# RS-485.net
KiCad netlist of a schematic drawn in Altium Designer
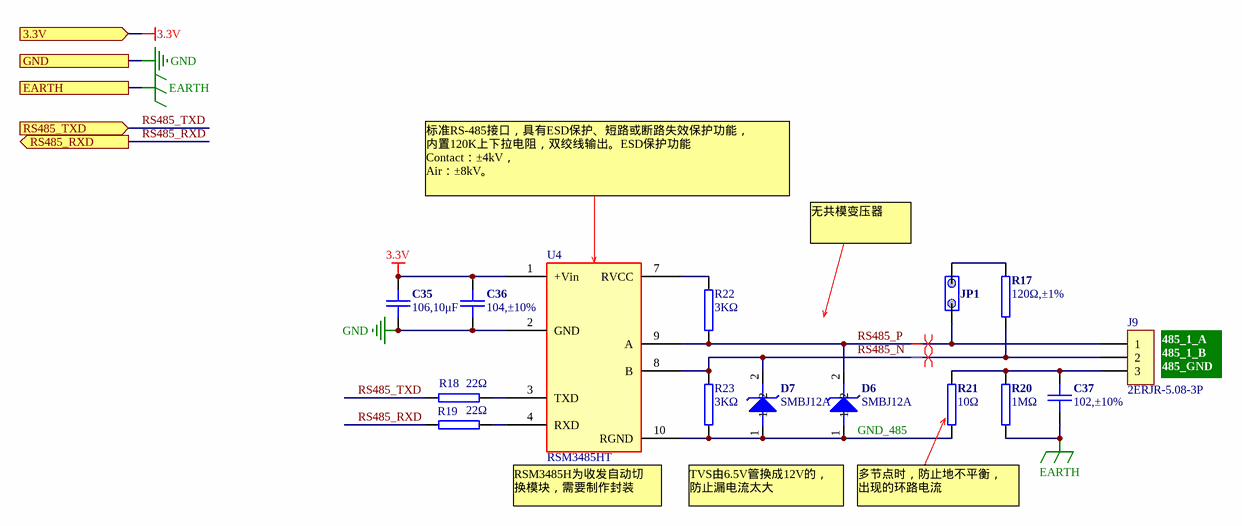
[diagram p0: RS-485推荐电路.SchDoc]

(export (version "E")
  (design (tool "Eeschema 10.0.6"))
  (components
    (comp (ref "C35")
      (value "106,10μF")
      (footprint "0805C")
      (description "106,10μF,±10%,10V,X5R,0805,RoHS")
      (libsource (lib "ErpMaterialData") (part "CAP1"))
    )
    (comp (ref "C36")
      (value "104,±10%")
      (footprint "0603C")
      (description "104,±10%,50V,X7R,0603,*,RoHS")
      (libsource (lib "ErpMaterialData") (part "CAP1"))
    )
    (comp (ref "C37")
      (value "102,±10%")
      (footprint "1206C")
      (description "102,±10%,2KV,X7R,1206,*,RoHS")
      (libsource (lib "ErpMaterialData") (part "CAP1"))
    )
    (comp (ref "D6")
      (value "SMBJ12A")
      (footprint "SOD-1812D")
      (description "SMBJ12A,DO-214AA,君耀,RoHS")
      (fields (field (name "Comment") "DIODE ZENER"))
      (libsource (lib "ErpMaterialData") (part "DIODE ZENER"))
    )
    (comp (ref "D7")
      (value "SMBJ12A")
      (footprint "SOD-1812D")
      (description "SMBJ12A,DO-214AA,君耀,RoHS")
      (fields (field (name "Comment") "DIODE ZENER"))
      (libsource (lib "ErpMaterialData") (part "DIODE ZENER"))
    )
    (comp (ref "J9")
      (value "2ERJR-5.08-3P")
      (footprint "CON-3-5.08")
      (fields (field (name "Comment") "CON3"))
      (libsource (lib "ErpMaterialData") (part "CON3"))
    )
    (comp (ref "JP1") (value "120Ω_EN") (footprint "SIP-2") (libsource (lib "无需物料号元件") (part "JMP2")))
    (comp (ref "R17")
      (value "120Ω,±1%")
      (footprint "1206R")
      (libsource (lib "ErpMaterialData") (part "RES2"))
    )
    (comp (ref "R18")
      (value "22Ω")
      (footprint "0603R")
      (description "22Ω,0603,*,RoHS")
      (libsource (lib "ErpMaterialData") (part "RES2"))
    )
    (comp (ref "R19")
      (value "22Ω")
      (footprint "0603R")
      (description "22Ω,0603,*,RoHS")
      (libsource (lib "ErpMaterialData") (part "RES2"))
    )
    (comp (ref "R20")
      (value "1MΩ")
      (footprint "1206R")
      (description "1MΩ,1206,RoHS")
      (libsource (lib "ErpMaterialData") (part "RES2"))
    )
    (comp (ref "R21")
      (value "10Ω")
      (footprint "0805R")
      (description "10Ω,0805,*,RoHS")
      (libsource (lib "ErpMaterialData") (part "RES2"))
    )
    (comp (ref "R22")
      (value "3KΩ")
      (footprint "0603R")
      (description "3KΩ,0603,*,RoHS")
      (libsource (lib "ErpMaterialData") (part "RES2"))
    )
    (comp (ref "R23")
      (value "3KΩ")
      (footprint "0603R")
      (description "3KΩ,0603,*,RoHS")
      (libsource (lib "ErpMaterialData") (part "RES2"))
    )
    (comp (ref "U4") (value "RSM3485HT") (libsource (lib "M6708_EV_BORAD") (part "RSM3485H")))
  )
  (nets
    (net (code "1") (name "/GND_485") (class "Default")
      (node (ref "D6") (pin "1") (pinfunction "1_1") (pintype "passive"))
      (node (ref "D7") (pin "1") (pinfunction "1_1") (pintype "passive"))
      (node (ref "R21") (pin "1") (pinfunction "1_1") (pintype "passive"))
      (node (ref "R23") (pin "2") (pinfunction "2_2") (pintype "passive"))
      (node (ref "U4") (pin "10") (pinfunction "RGND_10") (pintype "passive"))
    )
    (net (code "2") (name "/RS485_N") (class "Default")
      (node (ref "D7") (pin "2") (pinfunction "2_2") (pintype "passive"))
      (node (ref "J9") (pin "2") (pinfunction "2_2") (pintype "passive"))
      (node (ref "R17") (pin "2") (pinfunction "2_2") (pintype "passive"))
      (node (ref "R23") (pin "1") (pinfunction "1_1") (pintype "passive"))
      (node (ref "U4") (pin "8") (pinfunction "B_8") (pintype "passive"))
    )
    (net (code "3") (name "/RS485_P") (class "Default")
      (node (ref "D6") (pin "2") (pinfunction "2_2") (pintype "passive"))
      (node (ref "J9") (pin "1") (pinfunction "1_1") (pintype "passive"))
      (node (ref "JP1") (pin "1") (pinfunction "1_1") (pintype "passive"))
      (node (ref "R22") (pin "2") (pinfunction "2_2") (pintype "passive"))
      (node (ref "U4") (pin "9") (pinfunction "A_9") (pintype "passive"))
    )
    (net (code "4") (name "/RS485_RXD") (class "Default")
      (node (ref "R19") (pin "1") (pinfunction "1_1") (pintype "passive"))
    )
    (net (code "5") (name "/RS485_TXD") (class "Default")
      (node (ref "R18") (pin "1") (pinfunction "1_1") (pintype "passive"))
    )
    (net (code "6") (name "3.3V") (class "Default")
      (node (ref "C35") (pin "1") (pinfunction "1_1") (pintype "passive"))
      (node (ref "C36") (pin "1") (pinfunction "1_1") (pintype "passive"))
      (node (ref "U4") (pin "1") (pinfunction "+Vin_1") (pintype "passive"))
    )
    (net (code "7") (name "EARTH") (class "Default")
      (node (ref "C37") (pin "1") (pinfunction "1_1") (pintype "passive"))
      (node (ref "R20") (pin "2") (pinfunction "2_2") (pintype "passive"))
    )
    (net (code "8") (name "GND") (class "Default")
      (node (ref "C35") (pin "2") (pinfunction "2_2") (pintype "passive"))
      (node (ref "C36") (pin "2") (pinfunction "2_2") (pintype "passive"))
      (node (ref "U4") (pin "2") (pinfunction "GND_2") (pintype "passive"))
    )
    (net (code "9") (name "Net-(C37-Pad2)") (class "Default")
      (node (ref "C37") (pin "2") (pinfunction "2_2") (pintype "passive"))
      (node (ref "J9") (pin "3") (pinfunction "3_3") (pintype "passive"))
      (node (ref "R20") (pin "1") (pinfunction "1_1") (pintype "passive"))
      (node (ref "R21") (pin "2") (pinfunction "2_2") (pintype "passive"))
    )
    (net (code "10") (name "Net-(JP1-Pad2)") (class "Default")
      (node (ref "JP1") (pin "2") (pinfunction "2_2") (pintype "passive"))
      (node (ref "R17") (pin "1") (pinfunction "1_1") (pintype "passive"))
    )
    (net (code "11") (name "Net-(U4-RVCC)") (class "Default")
      (node (ref "R22") (pin "1") (pinfunction "1_1") (pintype "passive"))
      (node (ref "U4") (pin "7") (pinfunction "RVCC_7") (pintype "passive"))
    )
    (net (code "12") (name "Net-(U4-RXD)") (class "Default")
      (node (ref "R19") (pin "2") (pinfunction "2_2") (pintype "passive"))
      (node (ref "U4") (pin "4") (pinfunction "RXD_4") (pintype "passive"))
    )
    (net (code "13") (name "Net-(U4-TXD)") (class "Default")
      (node (ref "R18") (pin "2") (pinfunction "2_2") (pintype "passive"))
      (node (ref "U4") (pin "3") (pinfunction "TXD_3") (pintype "passive"))
    )
  )
)
